# ProDoc_TB6612.net
KiCad netlist of a schematic drawn in EasyEDA Pro
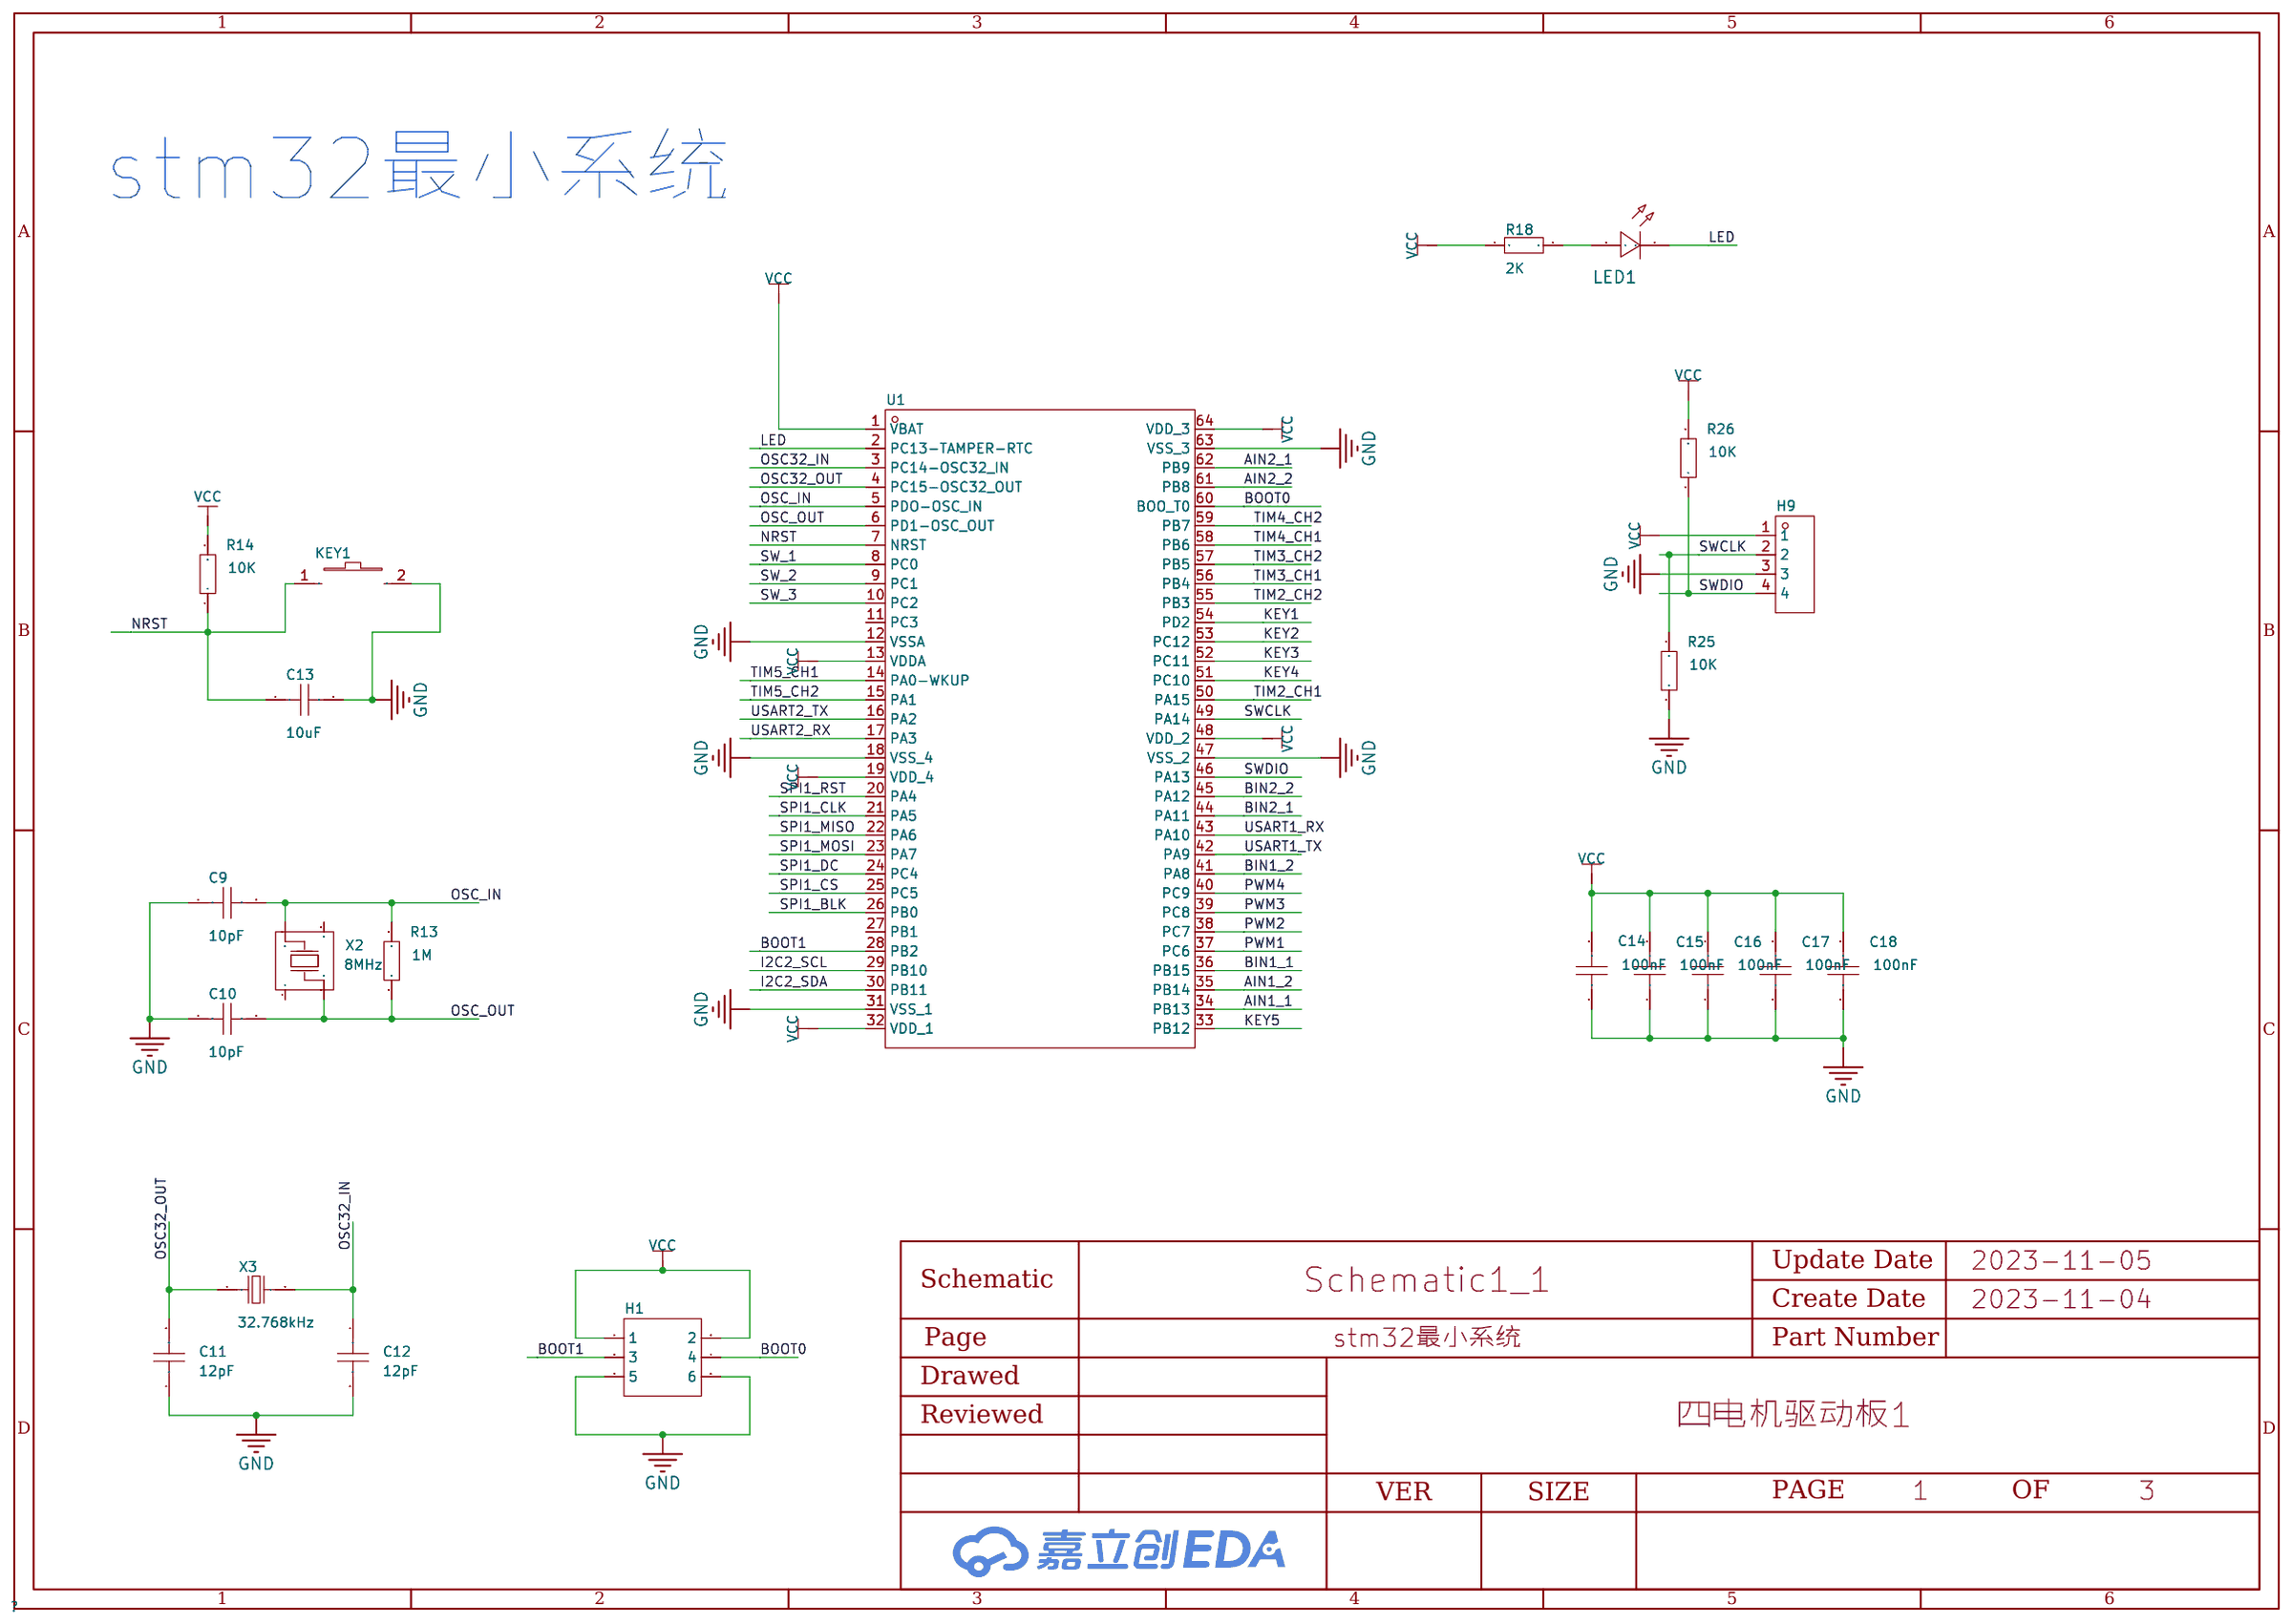
[diagram p0: stm32最小系统]
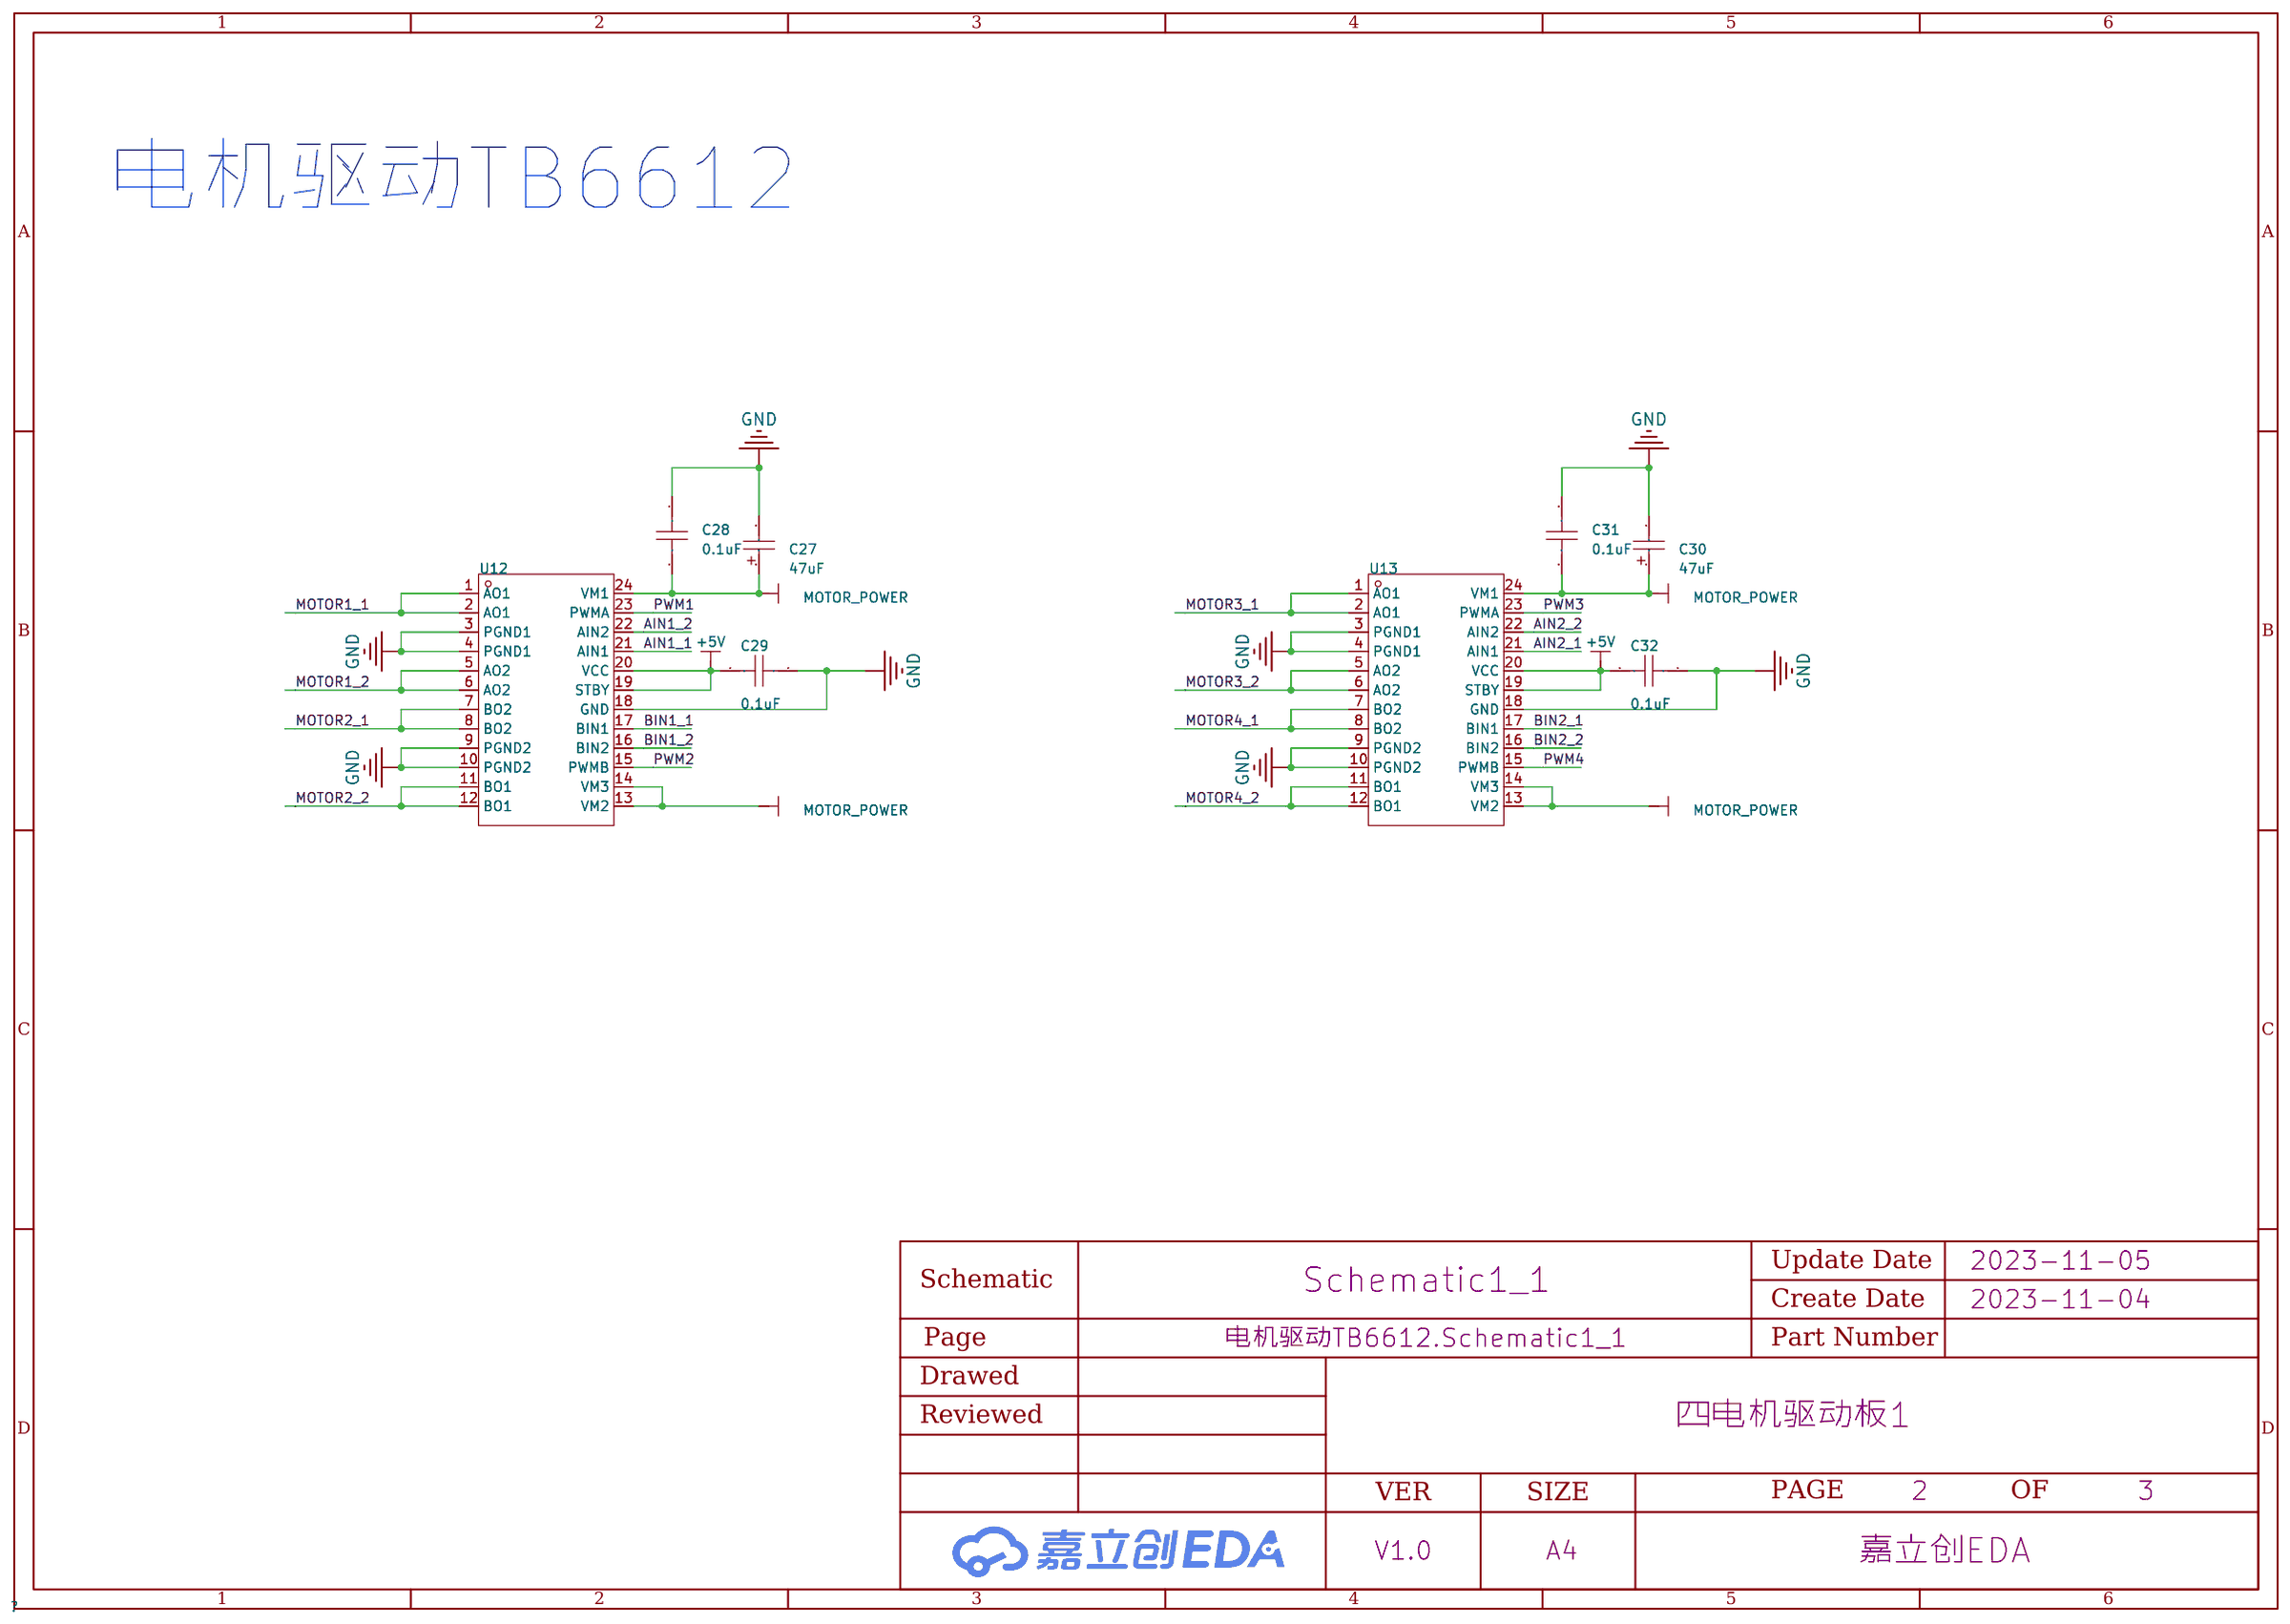
[diagram p1: 电机驱动TB6612]
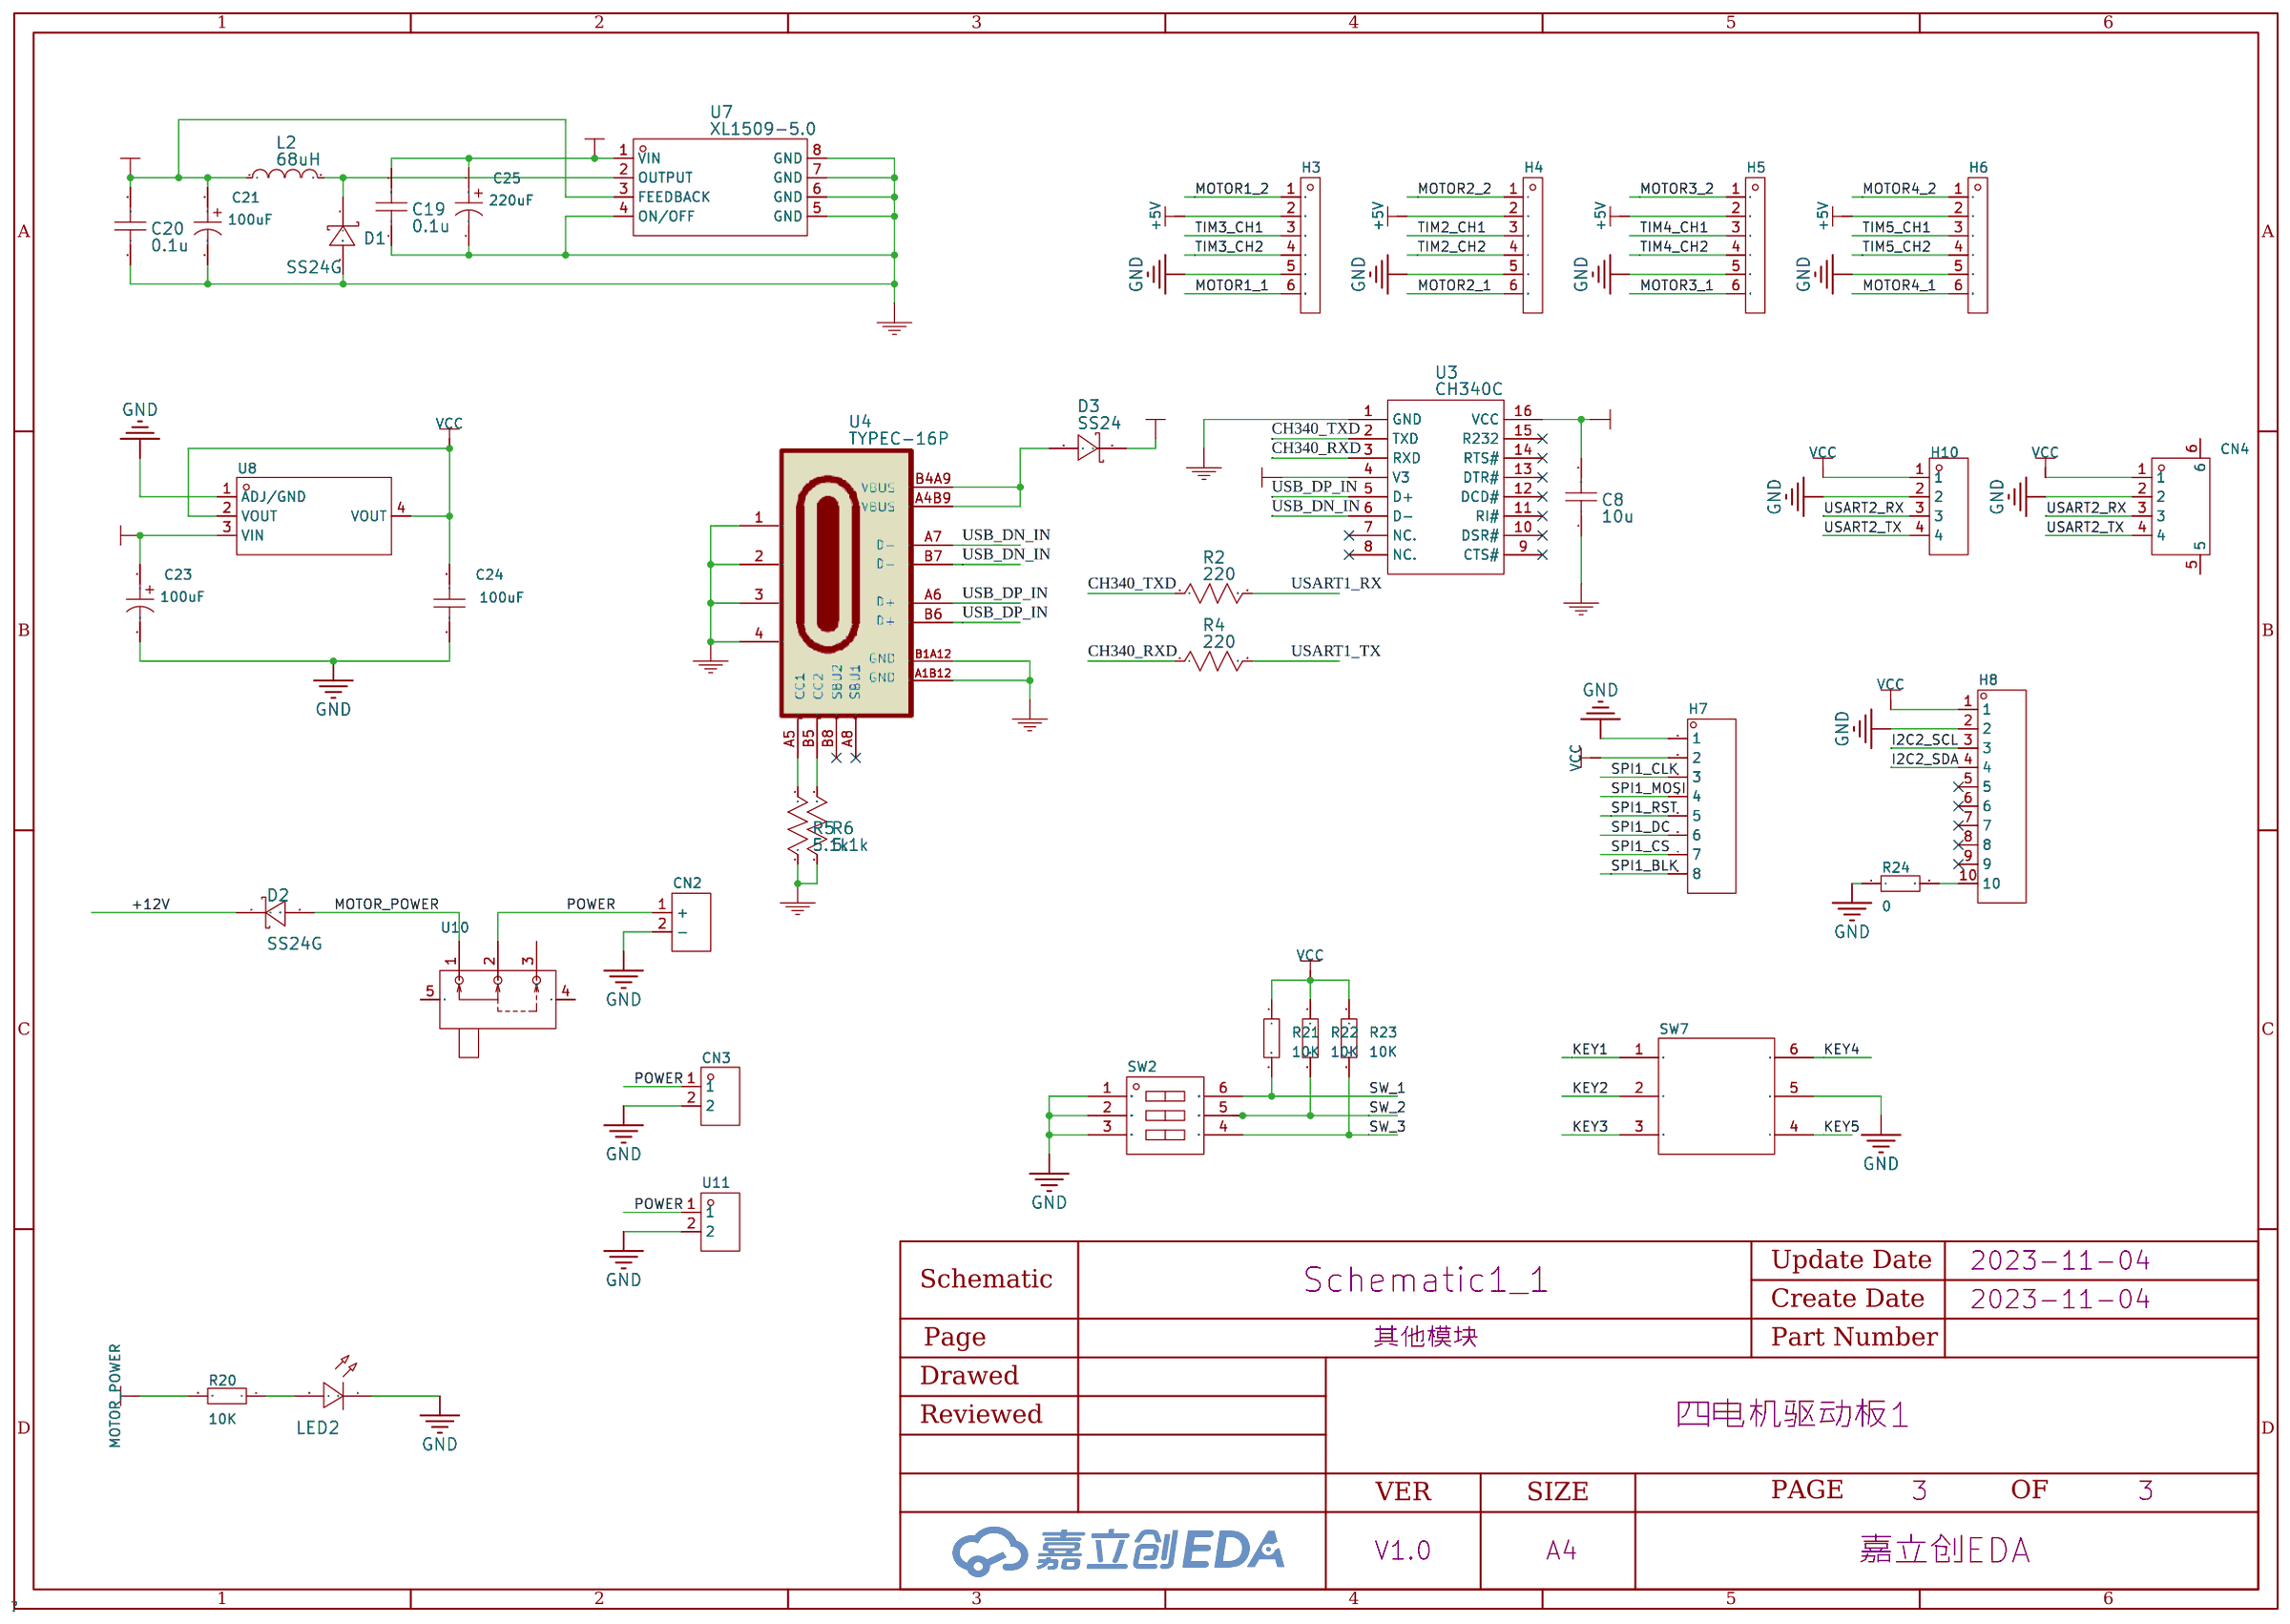
[diagram p2: 其他模块]

(export (version "E")
  (design (tool "Eeschema 10.0.6"))
  (components
    (comp (ref "C9")
      (value "10pF")
      (footprint "easyedapro:C0603")
      (libsource (lib "easyedapro") (part "C1210X7R475K630NT"))
    )
    (comp (ref "C10")
      (value "10pF")
      (footprint "easyedapro:C0603")
      (libsource (lib "easyedapro") (part "C1210X7R475K630NT"))
    )
    (comp (ref "C11")
      (value "12pF")
      (footprint "easyedapro:C0603")
      (libsource (lib "easyedapro") (part "C1210X7R475K630NT"))
    )
    (comp (ref "C12")
      (value "12pF")
      (footprint "easyedapro:C0603")
      (libsource (lib "easyedapro") (part "C1210X7R475K630NT"))
    )
    (comp (ref "C13")
      (value "10uF")
      (footprint "easyedapro:C0603")
      (fields
        (field (name "Manufacturer Part") "CC0603KRX7R9BB104")
        (field (name "Manufacturer") "YAGEO(国巨)")
        (field (name "Tolerance") "±10%")
      )
      (libsource (lib "easyedapro") (part "C1210X7R475K630NT"))
    )
    (comp (ref "C14")
      (value "100nF")
      (footprint "easyedapro:C0603")
      (libsource (lib "easyedapro") (part "C1210X7R475K630NT"))
    )
    (comp (ref "C15")
      (value "100nF")
      (footprint "easyedapro:C0603")
      (libsource (lib "easyedapro") (part "C1210X7R475K630NT"))
    )
    (comp (ref "C16")
      (value "100nF")
      (footprint "easyedapro:C0603")
      (libsource (lib "easyedapro") (part "C1210X7R475K630NT"))
    )
    (comp (ref "C17")
      (value "100nF")
      (footprint "easyedapro:C0603")
      (libsource (lib "easyedapro") (part "C1210X7R475K630NT"))
    )
    (comp (ref "C18")
      (value "100nF")
      (footprint "easyedapro:C0603")
      (libsource (lib "easyedapro") (part "C1210X7R475K630NT"))
    )
    (comp (ref "H1")
      (value "~")
      (footprint "easyedapro:HDR-TH_6P-P2.54-V-F-R2-C3-S2.54")
      (libsource (lib "easyedapro") (part "HDR-F-2.54_2x3"))
    )
    (comp (ref "H9")
      (value "~")
      (footprint "easyedapro:HDR-TH_4P-P2.54-V-M")
      (libsource (lib "easyedapro") (part "PZ254V-11-04P"))
    )
    (comp (ref "KEY1")
      (value "轻触开关3x4x2")
      (footprint "easyedapro:SW-SMD_L4.0-W2.9-LS5.0")
      (description "触点电流:50mA;额定电压(DC):12V;电路结构:单刀单掷;安装方式:立贴;按钮形状:圆形按钮;带灯:-;开关长度:4mm;开关宽度:3mm;开关高度:2mm;")
      (fields (field (name "Manufacturer") "国产"))
      (libsource (lib "easyedapro") (part "Switch3x4x2"))
    )
    (comp (ref "LED1")
      (value "~")
      (footprint "easyedapro:LED0805-RD_RED")
      (libsource (lib "easyedapro") (part "LED_R"))
    )
    (comp (ref "R13") (value "1M") (footprint "easyedapro:R0603") (libsource (lib "easyedapro") (part "电阻")))
    (comp (ref "R14") (value "10K") (footprint "easyedapro:R0603") (libsource (lib "easyedapro") (part "电阻")))
    (comp (ref "R18") (value "2K") (footprint "easyedapro:R0603") (libsource (lib "easyedapro") (part "电阻")))
    (comp (ref "R25") (value "10K") (footprint "easyedapro:R0603") (libsource (lib "easyedapro") (part "电阻")))
    (comp (ref "R26") (value "10K") (footprint "easyedapro:R0603") (libsource (lib "easyedapro") (part "电阻")))
    (comp (ref "U1")
      (value "~")
      (footprint "easyedapro:LQFP-64_L10.0-W10.0-P0.50-LS12.0-BL")
      (description "主频（MAX):72MHz;工作电压:2V ~ 3.6V;")
      (fields (field (name "Manufacturer Part") "STM32F103RCT6") (field (name "Manufacturer") "ST(意法半导体)"))
      (libsource (lib "easyedapro") (part "STM32F103RCT6"))
    )
    (comp (ref "X2")
      (value "8MHz")
      (footprint "easyedapro:OSC-SMD_4P-L3.2-W2.5-BL")
      (description "晶振类型:SMD 谐振器;频率:8MHz;频率公差:±10ppm;频率稳定度:±15ppm;负载电容:10pF;等效串联电阻(ESR):250Ω;工作温度:-;")
      (fields (field (name "Manufacturer Part") "TAXM8M4RDBCCT2T") (field (name "Manufacturer") "TAE(雅晶鑫)"))
      (libsource (lib "easyedapro") (part "TAXM8M4RDBCCT2T"))
    )
    (comp (ref "X3")
      (value "32.768kHz")
      (footprint "easyedapro:FC-135R_L3.2-W1.5")
      (description "晶振类型:贴片无源晶振;频率:32.768kHz;频率公差:±20ppm;负载电容:12.5pF;等效串联电阻(ESR):70kΩ;工作温度:-40~+85;")
      (fields (field (name "Manufacturer Part") "Q13FC1350000400") (field (name "Manufacturer") "EPSON(爱普生)"))
      (libsource (lib "easyedapro") (part "Q13FC1350000400"))
    )
    (comp (ref "C27")
      (value "47uF")
      (footprint "easyedapro:CAP-SMD_L6.0-W3.2-R-RD")
      (description "容值:47uF;精度:±10%;额定电压:16V;等效串联电阻:500mΩ@100kHz;")
      (fields (field (name "Manufacturer Part") "TAJC476K016RNJ") (field (name "Manufacturer") "Kyocera AVX"))
      (libsource (lib "easyedapro") (part "TAJC476K016RNJ"))
    )
    (comp (ref "C28")
      (value "0.1uF")
      (footprint "easyedapro:C0603")
      (libsource (lib "easyedapro") (part "C1210X7R475K630NT"))
    )
    (comp (ref "C29")
      (value "0.1uF")
      (footprint "easyedapro:C0603")
      (libsource (lib "easyedapro") (part "C1210X7R475K630NT"))
    )
    (comp (ref "C30")
      (value "47uF")
      (footprint "easyedapro:CAP-SMD_L6.0-W3.2-R-RD")
      (description "容值:47uF;精度:±10%;额定电压:16V;等效串联电阻:500mΩ@100kHz;")
      (fields (field (name "Manufacturer Part") "TAJC476K016RNJ") (field (name "Manufacturer") "Kyocera AVX"))
      (libsource (lib "easyedapro") (part "TAJC476K016RNJ"))
    )
    (comp (ref "C31")
      (value "0.1uF")
      (footprint "easyedapro:C0603")
      (libsource (lib "easyedapro") (part "C1210X7R475K630NT"))
    )
    (comp (ref "C32")
      (value "0.1uF")
      (footprint "easyedapro:C0603")
      (libsource (lib "easyedapro") (part "C1210X7R475K630NT"))
    )
    (comp (ref "U12")
      (value "TB6612FNG(O,C,8,EL")
      (footprint "easyedapro:SSOP-24_L8.4-W5.8-P0.65-LS7.8-BL")
      (description "双直流电机驱动器集成电路")
      (fields (field (name "Manufacturer") "TOSHIBA(东芝)"))
      (libsource (lib "easyedapro") (part "TB6612FNG(O,C,8,EL"))
    )
    (comp (ref "U13")
      (value "TB6612FNG(O,C,8,EL")
      (footprint "easyedapro:SSOP-24_L8.4-W5.8-P0.65-LS7.8-BL")
      (description "双直流电机驱动器集成电路")
      (fields (field (name "Manufacturer") "TOSHIBA(东芝)"))
      (libsource (lib "easyedapro") (part "TB6612FNG(O,C,8,EL"))
    )
    (comp (ref "C8") (value "10u") (footprint "easyedapro:C0603") (libsource (lib "easyedapro") (part "10u")))
    (comp (ref "C19")
      (value "0.1u")
      (footprint "easyedapro:C0603")
      (libsource (lib "easyedapro") (part "0.1u"))
    )
    (comp (ref "C20")
      (value "0.1u")
      (footprint "easyedapro:C0603")
      (libsource (lib "easyedapro") (part "0.1u"))
    )
    (comp (ref "C21")
      (value "100uF")
      (footprint "easyedapro:CAP-SMD_BD6.3-L6.6-W6.6-LS7.3-FD")
      (description "容值:100uF;精度:±20%;额定电压:16V;电容体直径:6.3mm;电容体长度:7.7mm;纹波电流:85mA@120Hz;工作寿命:2000hrs@105;工作温度:-55~+105;")
      (fields
        (field (name "Manufacturer Part") "XT100UF16V90RV0074")
        (field (name "Manufacturer") "KNSCHA(科尼盛)")
      )
      (libsource (lib "easyedapro") (part "XT100UF16V90RV0074"))
    )
    (comp (ref "C23")
      (value "100uF")
      (footprint "easyedapro:CAP-SMD_BD6.3-L6.6-W6.6-LS7.3-FD")
      (description "容值:100uF;精度:±20%;额定电压:16V;电容体直径:6.3mm;电容体长度:7.7mm;纹波电流:85mA@120Hz;工作寿命:2000hrs@105;工作温度:-55~+105;")
      (fields
        (field (name "Manufacturer Part") "XT100UF16V90RV0074")
        (field (name "Manufacturer") "KNSCHA(科尼盛)")
      )
      (libsource (lib "easyedapro") (part "XT100UF16V90RV0074"))
    )
    (comp (ref "C24")
      (value "100uF")
      (footprint "easyedapro:C0603")
      (libsource (lib "easyedapro") (part "C1210X7R475K630NT"))
    )
    (comp (ref "C25")
      (value "220uF")
      (footprint "easyedapro:CAP-SMD_BD6.3-L6.6-W6.6-LS7.3-FD")
      (description "容值:220uF;额定电压:25V;电容体直径:-;电容体长度:-;纹波电流:-;等效串联电阻:-;工作寿命:-;")
      (fields
        (field (name "Manufacturer Part") "XT220UF25V90RV0075")
        (field (name "Manufacturer") "KNSCHA(科尼盛)")
      )
      (libsource (lib "easyedapro") (part "XT220UF25V90RV0075"))
    )
    (comp (ref "CN2")
      (value "XT30UPB-F")
      (footprint "easyedapro:CONN-TH_XT30UPB-F")
      (description "模型插头连接器")
      (fields (field (name "Manufacturer") "AMASS(艾迈斯)"))
      (libsource (lib "easyedapro") (part "XT30UPB-F"))
    )
    (comp (ref "CN3")
      (value "XT30U-M")
      (footprint "easyedapro:CONN-TH_XT30U-M")
      (description "模型插头轻量版锂电池插头")
      (fields (field (name "Manufacturer") "AMASS(艾迈斯)"))
      (libsource (lib "easyedapro") (part "XT30U-M"))
    )
    (comp (ref "CN4")
      (value "PH-4P卧贴")
      (footprint "easyedapro:CONN-SMD_PH2.0-4PWB")
      (description "参考系列:PH;间距:2mm;插针结构:1x4P;排数:1;每排PIN数:4;行距:-;安装方式:-;触头材质:-;")
      (fields (field (name "Manufacturer") "BOOMELE(博穆精密)"))
      (libsource (lib "easyedapro") (part "PH2.0-4PWB卧式"))
    )
    (comp (ref "D1")
      (value "SS24G")
      (footprint "easyedapro:SMA_L4.4-W2.8-LS5.4-RD")
      (fields (field (name "Manufacturer") "SK"))
      (libsource (lib "easyedapro") (part "SS24G"))
    )
    (comp (ref "D2")
      (value "SS24G")
      (footprint "easyedapro:SMA_L4.4-W2.8-LS5.4-RD")
      (fields (field (name "Manufacturer") "SK"))
      (libsource (lib "easyedapro") (part "SS24G"))
    )
    (comp (ref "D3")
      (value "SS24")
      (footprint "easyedapro:SMA_L4.3-W2.6-LS5.2-RD")
      (fields (field (name "Manufacturer") "MDD"))
      (libsource (lib "easyedapro") (part "SS24"))
    )
    (comp (ref "H3")
      (value "~")
      (footprint "easyedapro:CONN-TH_XH-6AW")
      (description "参考系列:XH;间距:2.5mm;插针结构:1x6P;排数:1;每排PIN数:6;行距:-;安装方式:-;触头材质:-;")
      (fields (field (name "Manufacturer Part") "XH-6AW") (field (name "Manufacturer") "BOOMELE(博穆精密)"))
      (libsource (lib "easyedapro") (part "6P接插件"))
    )
    (comp (ref "H4")
      (value "~")
      (footprint "easyedapro:CONN-TH_XH-6AW")
      (description "参考系列:XH;间距:2.5mm;插针结构:1x6P;排数:1;每排PIN数:6;行距:-;安装方式:-;触头材质:-;")
      (fields (field (name "Manufacturer Part") "XH-6AW") (field (name "Manufacturer") "BOOMELE(博穆精密)"))
      (libsource (lib "easyedapro") (part "6P接插件"))
    )
    (comp (ref "H5")
      (value "~")
      (footprint "easyedapro:CONN-TH_XH-6AW")
      (description "参考系列:XH;间距:2.5mm;插针结构:1x6P;排数:1;每排PIN数:6;行距:-;安装方式:-;触头材质:-;")
      (fields (field (name "Manufacturer Part") "XH-6AW") (field (name "Manufacturer") "BOOMELE(博穆精密)"))
      (libsource (lib "easyedapro") (part "6P接插件"))
    )
    (comp (ref "H6")
      (value "~")
      (footprint "easyedapro:CONN-TH_XH-6AW")
      (description "参考系列:XH;间距:2.5mm;插针结构:1x6P;排数:1;每排PIN数:6;行距:-;安装方式:-;触头材质:-;")
      (fields (field (name "Manufacturer Part") "XH-6AW") (field (name "Manufacturer") "BOOMELE(博穆精密)"))
      (libsource (lib "easyedapro") (part "6P接插件"))
    )
    (comp (ref "H7")
      (value "~")
      (footprint "easyedapro:HDR-TH_8P-P2.54-V-M")
      (libsource (lib "easyedapro") (part "Header-Male-2.54_1x8"))
    )
    (comp (ref "H8")
      (value "~")
      (footprint "easyedapro:HDR-TH_10P-P2.54-V-M-1")
      (libsource (lib "easyedapro") (part "Header-Male-2.54_1x10"))
    )
    (comp (ref "H10")
      (value "~")
      (footprint "easyedapro:HDR-TH_4P-P2.54-V-F")
      (libsource (lib "easyedapro") (part "2.54-1*4P母"))
    )
    (comp (ref "L2")
      (value "68uH")
      (footprint "easyedapro:IND-SMD_L5.8-W5.2_CD54T125NP-100MC")
      (fields (field (name "Manufacturer Part") "CD54T125NP-100MC") (field (name "Manufacturer") "Sumida"))
      (libsource (lib "easyedapro") (part "68uH"))
    )
    (comp (ref "LED2")
      (value "~")
      (footprint "easyedapro:LED0805-RD_RED")
      (libsource (lib "easyedapro") (part "LED_R"))
    )
    (comp (ref "R2") (value "220") (footprint "easyedapro:R0603") (libsource (lib "easyedapro") (part "220")))
    (comp (ref "R4") (value "220") (footprint "easyedapro:R0603") (libsource (lib "easyedapro") (part "220")))
    (comp (ref "R5")
      (value "5.1k")
      (footprint "easyedapro:R0603")
      (libsource (lib "easyedapro") (part "5.1k"))
    )
    (comp (ref "R6")
      (value "5.1k")
      (footprint "easyedapro:R0603")
      (libsource (lib "easyedapro") (part "5.1k"))
    )
    (comp (ref "R20") (value "10K") (footprint "easyedapro:R0603") (libsource (lib "easyedapro") (part "电阻")))
    (comp (ref "R21") (value "10K") (footprint "easyedapro:R0603") (libsource (lib "easyedapro") (part "电阻")))
    (comp (ref "R22") (value "10K") (footprint "easyedapro:R0603") (libsource (lib "easyedapro") (part "电阻")))
    (comp (ref "R23") (value "10K") (footprint "easyedapro:R0603") (libsource (lib "easyedapro") (part "电阻")))
    (comp (ref "R24") (value "0") (footprint "easyedapro:R0603") (libsource (lib "easyedapro") (part "电阻")))
    (comp (ref "SW2")
      (value "TO-03")
      (footprint "easyedapro:SW-SMD_6P-L7.6-W6.3-P2.54-LS9.8")
      (description "拨码开关贴片黑色03P-3PIN间距2.54mm立式贴片正拨平拨3位SMD")
      (fields (field (name "Manufacturer") "Yuandi(台湾元迪)"))
      (libsource (lib "easyedapro") (part "TO-03"))
    )
    (comp (ref "SW7")
      (value "7*7*5-6P-L WX")
      (footprint "easyedapro:SW-SMD_6P-L7.0-W7.0-P1.40-LS7.4")
      (fields (field (name "Manufacturer") "SHOU HAN(首韩)"))
      (libsource (lib "easyedapro") (part "7*7*5-6P-L WX"))
    )
    (comp (ref "U3")
      (value "CH340C")
      (footprint "easyedapro:SOP-16_L10.0-W3.9-P1.27-LS6.0-BL")
      (fields (field (name "Manufacturer") "WCH(南京沁恒)"))
      (libsource (lib "easyedapro") (part "CH340C"))
    )
    (comp (ref "U4")
      (value "TYPEC-16P")
      (footprint "easyedapro:TYPEC")
      (libsource (lib "easyedapro") (part "TYPEC-16P"))
    )
    (comp (ref "U7")
      (value "XL1509-5.0")
      (footprint "easyedapro:SOIC-8_L5.0-W4.0-P1.27-LS6.0-BL")
      (fields (field (name "Manufacturer") "UMW(友台半导体)"))
      (libsource (lib "easyedapro") (part "XL1509-5.0"))
    )
    (comp (ref "U8")
      (value "AMS1117-3.3")
      (footprint "easyedapro:SOT-223_L6.5-W3.5-P2.30-LS7.0-BR")
      (fields (field (name "Manufacturer") "PUOLOP(迪浦)"))
      (libsource (lib "easyedapro") (part "AMS1117-3.3_C351785"))
    )
    (comp (ref "U10")
      (value "SS-12F23-G4")
      (footprint "easyedapro:SW-TH_SS-12F23-G040")
      (description "电路结构:单刀双掷;安装方式:卧插;开关颜色:黑色;滑钮形状:矩形柱状;引脚样式:PC引脚;开关长度:13mm;开关宽度:5.8mm;开关高度:9mm;")
      (fields (field (name "Manufacturer") "DEALON(德艺隆)"))
      (libsource (lib "easyedapro") (part "SS-12F23-G4"))
    )
    (comp (ref "U11")
      (value "KF127-5.08-2P")
      (footprint "easyedapro:CONN-TH_P5.08_KF127-5.08-2P")
      (fields (field (name "Manufacturer") "KEFA(科发)"))
      (libsource (lib "easyedapro") (part "KF127-5.08-2P"))
    )
  )
  (nets
    (net (code "1") (name "+5V") (class "Default")
      (node (ref "C20") (pin "2") (pinfunction "2_2") (pintype "input"))
      (node (ref "C21") (pin "1") (pinfunction "1_1") (pintype "input"))
      (node (ref "C23") (pin "1") (pinfunction "1_1") (pintype "input"))
      (node (ref "C29") (pin "2") (pinfunction "2_2") (pintype "input"))
      (node (ref "C32") (pin "2") (pinfunction "2_2") (pintype "input"))
      (node (ref "D3") (pin "1") (pinfunction "K_1") (pintype "input"))
      (node (ref "H3") (pin "2") (pinfunction "2_2") (pintype "input"))
      (node (ref "H4") (pin "2") (pinfunction "2_2") (pintype "input"))
      (node (ref "H5") (pin "2") (pinfunction "2_2") (pintype "input"))
      (node (ref "H6") (pin "2") (pinfunction "2_2") (pintype "input"))
      (node (ref "L2") (pin "1") (pinfunction "1_1") (pintype "input"))
      (node (ref "U12") (pin "19") (pinfunction "STBY_19") (pintype "input"))
      (node (ref "U12") (pin "20") (pinfunction "VCC_20") (pintype "input"))
      (node (ref "U13") (pin "19") (pinfunction "STBY_19") (pintype "input"))
      (node (ref "U13") (pin "20") (pinfunction "VCC_20") (pintype "input"))
      (node (ref "U7") (pin "3") (pinfunction "FEEDBACK_3") (pintype "input"))
      (node (ref "U8") (pin "3") (pinfunction "VIN_3") (pintype "input"))
    )
    (net (code "2") (name "+12V") (class "Default")
      (node (ref "C19") (pin "2") (pinfunction "2_2") (pintype "input"))
      (node (ref "C25") (pin "1") (pinfunction "1_1") (pintype "input"))
      (node (ref "D2") (pin "1") (pinfunction "1_1") (pintype "input"))
      (node (ref "U7") (pin "1") (pinfunction "VIN_1") (pintype "input"))
    )
    (net (code "3") (name "AIN1_1") (class "Default")
      (node (ref "U1") (pin "34") (pinfunction "PB13_34") (pintype "input"))
      (node (ref "U12") (pin "21") (pinfunction "AIN1_21") (pintype "input"))
    )
    (net (code "4") (name "AIN1_2") (class "Default")
      (node (ref "U1") (pin "35") (pinfunction "PB14_35") (pintype "input"))
      (node (ref "U12") (pin "22") (pinfunction "AIN2_22") (pintype "input"))
    )
    (net (code "5") (name "AIN2_1") (class "Default")
      (node (ref "U1") (pin "62") (pinfunction "PB9_62") (pintype "input"))
      (node (ref "U13") (pin "21") (pinfunction "AIN1_21") (pintype "input"))
    )
    (net (code "6") (name "AIN2_2") (class "Default")
      (node (ref "U1") (pin "61") (pinfunction "PB8_61") (pintype "input"))
      (node (ref "U13") (pin "22") (pinfunction "AIN2_22") (pintype "input"))
    )
    (net (code "7") (name "BIN1_1") (class "Default")
      (node (ref "U1") (pin "36") (pinfunction "PB15_36") (pintype "input"))
      (node (ref "U12") (pin "17") (pinfunction "BIN1_17") (pintype "input"))
    )
    (net (code "8") (name "BIN1_2") (class "Default")
      (node (ref "U1") (pin "41") (pinfunction "PA8_41") (pintype "input"))
      (node (ref "U12") (pin "16") (pinfunction "BIN2_16") (pintype "input"))
    )
    (net (code "9") (name "BIN2_1") (class "Default")
      (node (ref "U1") (pin "44") (pinfunction "PA11_44") (pintype "input"))
      (node (ref "U13") (pin "17") (pinfunction "BIN1_17") (pintype "input"))
    )
    (net (code "10") (name "BIN2_2") (class "Default")
      (node (ref "U1") (pin "45") (pinfunction "PA12_45") (pintype "input"))
      (node (ref "U13") (pin "16") (pinfunction "BIN2_16") (pintype "input"))
    )
    (net (code "11") (name "BOOT0") (class "Default")
      (node (ref "H1") (pin "4") (pinfunction "4_4") (pintype "input"))
      (node (ref "U1") (pin "60") (pinfunction "BOO_T0_60") (pintype "input"))
    )
    (net (code "12") (name "BOOT1") (class "Default")
      (node (ref "H1") (pin "3") (pinfunction "3_3") (pintype "input"))
      (node (ref "U1") (pin "28") (pinfunction "PB2_28") (pintype "input"))
    )
    (net (code "13") (name "CH340_RXD") (class "Default")
      (node (ref "R4") (pin "1") (pinfunction "1_1") (pintype "input"))
      (node (ref "U3") (pin "3") (pinfunction "RXD_3") (pintype "input"))
    )
    (net (code "14") (name "CH340_TXD") (class "Default")
      (node (ref "R2") (pin "1") (pinfunction "1_1") (pintype "input"))
      (node (ref "U3") (pin "2") (pinfunction "TXD_2") (pintype "input"))
    )
    (net (code "15") (name "GND") (class "Default")
      (node (ref "C10") (pin "1") (pinfunction "1_1") (pintype "input"))
      (node (ref "C11") (pin "1") (pinfunction "1_1") (pintype "input"))
      (node (ref "C12") (pin "2") (pinfunction "2_2") (pintype "input"))
      (node (ref "C13") (pin "2") (pinfunction "2_2") (pintype "input"))
      (node (ref "C14") (pin "1") (pinfunction "1_1") (pintype "input"))
      (node (ref "C15") (pin "1") (pinfunction "1_1") (pintype "input"))
      (node (ref "C16") (pin "1") (pinfunction "1_1") (pintype "input"))
      (node (ref "C17") (pin "1") (pinfunction "1_1") (pintype "input"))
      (node (ref "C18") (pin "1") (pinfunction "1_1") (pintype "input"))
      (node (ref "C19") (pin "1") (pinfunction "1_1") (pintype "input"))
      (node (ref "C20") (pin "1") (pinfunction "1_1") (pintype "input"))
      (node (ref "C21") (pin "2") (pinfunction "2_2") (pintype "input"))
      (node (ref "C23") (pin "2") (pinfunction "2_2") (pintype "input"))
      (node (ref "C24") (pin "1") (pinfunction "1_1") (pintype "input"))
      (node (ref "C25") (pin "2") (pinfunction "2_2") (pintype "input"))
      (node (ref "C27") (pin "2") (pinfunction "2_2") (pintype "input"))
      (node (ref "C28") (pin "1") (pinfunction "1_1") (pintype "input"))
      (node (ref "C29") (pin "1") (pinfunction "1_1") (pintype "input"))
      (node (ref "C30") (pin "2") (pinfunction "2_2") (pintype "input"))
      (node (ref "C31") (pin "1") (pinfunction "1_1") (pintype "input"))
      (node (ref "C32") (pin "1") (pinfunction "1_1") (pintype "input"))
      (node (ref "C8") (pin "1") (pinfunction "1_1") (pintype "input"))
      (node (ref "C9") (pin "1") (pinfunction "1_1") (pintype "input"))
      (node (ref "CN2") (pin "2") (pinfunction "-_2") (pintype "input"))
      (node (ref "CN3") (pin "2") (pinfunction "2_2") (pintype "input"))
      (node (ref "CN4") (pin "2") (pinfunction "2_2") (pintype "input"))
      (node (ref "D1") (pin "2") (pinfunction "2_2") (pintype "input"))
      (node (ref "H1") (pin "5") (pinfunction "5_5") (pintype "input"))
      (node (ref "H1") (pin "6") (pinfunction "6_6") (pintype "input"))
      (node (ref "H10") (pin "2") (pinfunction "2_2") (pintype "unspecified"))
      (node (ref "H3") (pin "5") (pinfunction "5_5") (pintype "input"))
      (node (ref "H4") (pin "5") (pinfunction "5_5") (pintype "input"))
      (node (ref "H5") (pin "5") (pinfunction "5_5") (pintype "input"))
      (node (ref "H6") (pin "5") (pinfunction "5_5") (pintype "input"))
      (node (ref "H7") (pin "1") (pinfunction "1_1") (pintype "input"))
      (node (ref "H8") (pin "2") (pinfunction "2_2") (pintype "input"))
      (node (ref "H9") (pin "3") (pinfunction "3_3") (pintype "input"))
      (node (ref "KEY1") (pin "2") (pinfunction "2_2") (pintype "input"))
      (node (ref "LED2") (pin "1") (pinfunction "C_1") (pintype "input"))
      (node (ref "R24") (pin "1") (pinfunction "1_1") (pintype "input"))
      (node (ref "R25") (pin "1") (pinfunction "1_1") (pintype "input"))
      (node (ref "R5") (pin "1") (pinfunction "1_1") (pintype "input"))
      (node (ref "R6") (pin "1") (pinfunction "1_1") (pintype "input"))
      (node (ref "SW2") (pin "1") (pinfunction "PIN1_1") (pintype "input"))
      (node (ref "SW2") (pin "2") (pinfunction "PIN2_2") (pintype "input"))
      (node (ref "SW2") (pin "3") (pinfunction "PIN3_3") (pintype "input"))
      (node (ref "SW7") (pin "5") (pinfunction "5_5") (pintype "input"))
      (node (ref "U1") (pin "12") (pinfunction "VSSA_12") (pintype "input"))
      (node (ref "U1") (pin "18") (pinfunction "VSS_4_18") (pintype "input"))
      (node (ref "U1") (pin "31") (pinfunction "VSS_1_31") (pintype "input"))
      (node (ref "U1") (pin "47") (pinfunction "VSS_2_47") (pintype "input"))
      (node (ref "U1") (pin "63") (pinfunction "VSS_3_63") (pintype "input"))
      (node (ref "U11") (pin "2") (pinfunction "2_2") (pintype "input"))
      (node (ref "U12") (pin "10") (pinfunction "PGND2_10") (pintype "input"))
      (node (ref "U12") (pin "18") (pinfunction "GND_18") (pintype "input"))
      (node (ref "U12") (pin "3") (pinfunction "PGND1_3") (pintype "input"))
      (node (ref "U12") (pin "4") (pinfunction "PGND1_4") (pintype "input"))
      (node (ref "U12") (pin "9") (pinfunction "PGND2_9") (pintype "input"))
      (node (ref "U13") (pin "10") (pinfunction "PGND2_10") (pintype "input"))
      (node (ref "U13") (pin "18") (pinfunction "GND_18") (pintype "input"))
      (node (ref "U13") (pin "3") (pinfunction "PGND1_3") (pintype "input"))
      (node (ref "U13") (pin "4") (pinfunction "PGND1_4") (pintype "input"))
      (node (ref "U13") (pin "9") (pinfunction "PGND2_9") (pintype "input"))
      (node (ref "U3") (pin "1") (pinfunction "GND_1") (pintype "input"))
      (node (ref "U4") (pin "1") (pinfunction "1_1") (pintype "input"))
      (node (ref "U4") (pin "2") (pinfunction "1_2") (pintype "input"))
      (node (ref "U4") (pin "3") (pinfunction "1_3") (pintype "input"))
      (node (ref "U4") (pin "4") (pinfunction "1_4") (pintype "input"))
      (node (ref "U4") (pin "A1B12") (pinfunction "1_A1B12") (pintype "input"))
      (node (ref "U4") (pin "B1A12") (pinfunction "1_B1A12") (pintype "input"))
      (node (ref "U7") (pin "4") (pinfunction "ON/OFF_4") (pintype "input"))
      (node (ref "U7") (pin "5") (pinfunction "GND_5") (pintype "input"))
      (node (ref "U7") (pin "6") (pinfunction "GND_6") (pintype "input"))
      (node (ref "U7") (pin "7") (pinfunction "GND_7") (pintype "input"))
      (node (ref "U7") (pin "8") (pinfunction "GND_8") (pintype "input"))
      (node (ref "U8") (pin "1") (pinfunction "ADJ/GND_1") (pintype "input"))
    )
    (net (code "16") (name "I2C2_SCL") (class "Default")
      (node (ref "H8") (pin "3") (pinfunction "3_3") (pintype "input"))
      (node (ref "U1") (pin "29") (pinfunction "PB10_29") (pintype "input"))
    )
    (net (code "17") (name "I2C2_SDA") (class "Default")
      (node (ref "H8") (pin "4") (pinfunction "4_4") (pintype "input"))
      (node (ref "U1") (pin "30") (pinfunction "PB11_30") (pintype "input"))
    )
    (net (code "18") (name "KEY1") (class "Default")
      (node (ref "SW7") (pin "1") (pinfunction "1_1") (pintype "input"))
      (node (ref "U1") (pin "54") (pinfunction "PD2_54") (pintype "input"))
    )
    (net (code "19") (name "KEY2") (class "Default")
      (node (ref "SW7") (pin "2") (pinfunction "2_2") (pintype "input"))
      (node (ref "U1") (pin "53") (pinfunction "PC12_53") (pintype "input"))
    )
    (net (code "20") (name "KEY3") (class "Default")
      (node (ref "SW7") (pin "3") (pinfunction "3_3") (pintype "input"))
      (node (ref "U1") (pin "52") (pinfunction "PC11_52") (pintype "input"))
    )
    (net (code "21") (name "KEY4") (class "Default")
      (node (ref "SW7") (pin "6") (pinfunction "6_6") (pintype "input"))
      (node (ref "U1") (pin "51") (pinfunction "PC10_51") (pintype "input"))
    )
    (net (code "22") (name "KEY5") (class "Default")
      (node (ref "SW7") (pin "4") (pinfunction "4_4") (pintype "input"))
      (node (ref "U1") (pin "33") (pinfunction "PB12_33") (pintype "input"))
    )
    (net (code "23") (name "LED") (class "Default")
      (node (ref "LED1") (pin "1") (pinfunction "C_1") (pintype "input"))
      (node (ref "U1") (pin "2") (pinfunction "PC13-TAMPER-RTC_2") (pintype "input"))
    )
    (net (code "24") (name "MOTOR1_1") (class "Default")
      (node (ref "H3") (pin "6") (pinfunction "6_6") (pintype "input"))
      (node (ref "U12") (pin "1") (pinfunction "AO1_1") (pintype "input"))
      (node (ref "U12") (pin "2") (pinfunction "AO1_2") (pintype "input"))
    )
    (net (code "25") (name "MOTOR1_2") (class "Default")
      (node (ref "H3") (pin "1") (pinfunction "1_1") (pintype "input"))
      (node (ref "U12") (pin "5") (pinfunction "AO2_5") (pintype "input"))
      (node (ref "U12") (pin "6") (pinfunction "AO2_6") (pintype "input"))
    )
    (net (code "26") (name "MOTOR2_1") (class "Default")
      (node (ref "H4") (pin "6") (pinfunction "6_6") (pintype "input"))
      (node (ref "U12") (pin "7") (pinfunction "BO2_7") (pintype "input"))
      (node (ref "U12") (pin "8") (pinfunction "BO2_8") (pintype "input"))
    )
    (net (code "27") (name "MOTOR2_2") (class "Default")
      (node (ref "H4") (pin "1") (pinfunction "1_1") (pintype "input"))
      (node (ref "U12") (pin "11") (pinfunction "BO1_11") (pintype "input"))
      (node (ref "U12") (pin "12") (pinfunction "BO1_12") (pintype "input"))
    )
    (net (code "28") (name "MOTOR3_1") (class "Default")
      (node (ref "H5") (pin "6") (pinfunction "6_6") (pintype "input"))
      (node (ref "U13") (pin "1") (pinfunction "AO1_1") (pintype "input"))
      (node (ref "U13") (pin "2") (pinfunction "AO1_2") (pintype "input"))
    )
    (net (code "29") (name "MOTOR3_2") (class "Default")
      (node (ref "H5") (pin "1") (pinfunction "1_1") (pintype "input"))
      (node (ref "U13") (pin "5") (pinfunction "AO2_5") (pintype "input"))
      (node (ref "U13") (pin "6") (pinfunction "AO2_6") (pintype "input"))
    )
    (net (code "30") (name "MOTOR4_1") (class "Default")
      (node (ref "H6") (pin "6") (pinfunction "6_6") (pintype "input"))
      (node (ref "U13") (pin "7") (pinfunction "BO2_7") (pintype "input"))
      (node (ref "U13") (pin "8") (pinfunction "BO2_8") (pintype "input"))
    )
    (net (code "31") (name "MOTOR4_2") (class "Default")
      (node (ref "H6") (pin "1") (pinfunction "1_1") (pintype "input"))
      (node (ref "U13") (pin "11") (pinfunction "BO1_11") (pintype "input"))
      (node (ref "U13") (pin "12") (pinfunction "BO1_12") (pintype "input"))
    )
    (net (code "32") (name "MOTOR_POWER") (class "Default")
      (node (ref "C27") (pin "1") (pinfunction "1_1") (pintype "input"))
      (node (ref "C28") (pin "2") (pinfunction "2_2") (pintype "input"))
      (node (ref "C30") (pin "1") (pinfunction "1_1") (pintype "input"))
      (node (ref "C31") (pin "2") (pinfunction "2_2") (pintype "input"))
      (node (ref "D2") (pin "2") (pinfunction "2_2") (pintype "input"))
      (node (ref "R20") (pin "2") (pinfunction "2_2") (pintype "input"))
      (node (ref "U10") (pin "1") (pinfunction "1_1") (pintype "input"))
      (node (ref "U12") (pin "13") (pinfunction "VM2_13") (pintype "input"))
      (node (ref "U12") (pin "14") (pinfunction "VM3_14") (pintype "input"))
      (node (ref "U12") (pin "24") (pinfunction "VM1_24") (pintype "input"))
      (node (ref "U13") (pin "13") (pinfunction "VM2_13") (pintype "input"))
      (node (ref "U13") (pin "14") (pinfunction "VM3_14") (pintype "input"))
      (node (ref "U13") (pin "24") (pinfunction "VM1_24") (pintype "input"))
    )
    (net (code "33") (name "NRST") (class "Default")
      (node (ref "C13") (pin "1") (pinfunction "1_1") (pintype "input"))
      (node (ref "KEY1") (pin "1") (pinfunction "1_1") (pintype "input"))
      (node (ref "R14") (pin "1") (pinfunction "1_1") (pintype "input"))
      (node (ref "U1") (pin "7") (pinfunction "NRST_7") (pintype "input"))
    )
    (net (code "34") (name "Net-(D3-A)") (class "Default")
      (node (ref "D3") (pin "2") (pinfunction "A_2") (pintype "input"))
      (node (ref "U4") (pin "A4B9") (pinfunction "1_A4B9") (pintype "input"))
      (node (ref "U4") (pin "B4A9") (pinfunction "1_B4A9") (pintype "input"))
    )
    (net (code "35") (name "Net-(H8-Pad10)") (class "Default")
      (node (ref "H8") (pin "10") (pinfunction "10_10") (pintype "input"))
      (node (ref "R24") (pin "2") (pinfunction "2_2") (pintype "input"))
    )
    (net (code "36") (name "Net-(LED1-A)") (class "Default")
      (node (ref "LED1") (pin "2") (pinfunction "A_2") (pintype "input"))
      (node (ref "R18") (pin "1") (pinfunction "1_1") (pintype "input"))
    )
    (net (code "37") (name "Net-(LED2-A)") (class "Default")
      (node (ref "LED2") (pin "2") (pinfunction "A_2") (pintype "input"))
      (node (ref "R20") (pin "1") (pinfunction "1_1") (pintype "input"))
    )
    (net (code "38") (name "Net-(R5-Pad2)") (class "Default")
      (node (ref "R5") (pin "2") (pinfunction "2_2") (pintype "input"))
      (node (ref "U4") (pin "A5") (pinfunction "1_A5") (pintype "input"))
    )
    (net (code "39") (name "Net-(R6-Pad2)") (class "Default")
      (node (ref "R6") (pin "2") (pinfunction "2_2") (pintype "input"))
      (node (ref "U4") (pin "B5") (pinfunction "1_B5") (pintype "input"))
    )
    (net (code "40") (name "Net-(U7-OUTPUT)") (class "Default")
      (node (ref "D1") (pin "1") (pinfunction "1_1") (pintype "input"))
      (node (ref "L2") (pin "2") (pinfunction "2_2") (pintype "input"))
      (node (ref "U7") (pin "2") (pinfunction "OUTPUT_2") (pintype "input"))
    )
    (net (code "41") (name "OSC32_IN") (class "Default")
      (node (ref "C12") (pin "1") (pinfunction "1_1") (pintype "input"))
      (node (ref "U1") (pin "3") (pinfunction "PC14-OSC32_IN_3") (pintype "input"))
      (node (ref "X3") (pin "2") (pinfunction "2_2") (pintype "input"))
    )
    (net (code "42") (name "OSC32_OUT") (class "Default")
      (node (ref "C11") (pin "2") (pinfunction "2_2") (pintype "input"))
      (node (ref "U1") (pin "4") (pinfunction "PC15-OSC32_OUT_4") (pintype "input"))
      (node (ref "X3") (pin "1") (pinfunction "1_1") (pintype "input"))
    )
    (net (code "43") (name "OSC_IN") (class "Default")
      (node (ref "C9") (pin "2") (pinfunction "2_2") (pintype "input"))
      (node (ref "R13") (pin "2") (pinfunction "2_2") (pintype "input"))
      (node (ref "U1") (pin "5") (pinfunction "PDO-OSC_IN_5") (pintype "input"))
      (node (ref "X2") (pin "3") (pinfunction "3_3") (pintype "input"))
    )
    (net (code "44") (name "OSC_OUT") (class "Default")
      (node (ref "C10") (pin "2") (pinfunction "2_2") (pintype "input"))
      (node (ref "R13") (pin "1") (pinfunction "1_1") (pintype "input"))
      (node (ref "U1") (pin "6") (pinfunction "PD1-OSC_OUT_6") (pintype "input"))
      (node (ref "X2") (pin "1") (pinfunction "1_1") (pintype "input"))
    )
    (net (code "45") (name "POWER") (class "Default")
      (node (ref "CN2") (pin "1") (pinfunction "+_1") (pintype "input"))
      (node (ref "CN3") (pin "1") (pinfunction "1_1") (pintype "input"))
      (node (ref "U10") (pin "2") (pinfunction "2_2") (pintype "input"))
      (node (ref "U11") (pin "1") (pinfunction "1_1") (pintype "input"))
    )
    (net (code "46") (name "PWM1") (class "Default")
      (node (ref "U1") (pin "37") (pinfunction "PC6_37") (pintype "input"))
      (node (ref "U12") (pin "23") (pinfunction "PWMA_23") (pintype "input"))
    )
    (net (code "47") (name "PWM2") (class "Default")
      (node (ref "U1") (pin "38") (pinfunction "PC7_38") (pintype "input"))
      (node (ref "U12") (pin "15") (pinfunction "PWMB_15") (pintype "input"))
    )
    (net (code "48") (name "PWM3") (class "Default")
      (node (ref "U1") (pin "39") (pinfunction "PC8_39") (pintype "input"))
      (node (ref "U13") (pin "23") (pinfunction "PWMA_23") (pintype "input"))
    )
    (net (code "49") (name "PWM4") (class "Default")
      (node (ref "U1") (pin "40") (pinfunction "PC9_40") (pintype "input"))
      (node (ref "U13") (pin "15") (pinfunction "PWMB_15") (pintype "input"))
    )
    (net (code "50") (name "SPI1_BLK") (class "Default")
      (node (ref "H7") (pin "8") (pinfunction "8_8") (pintype "input"))
      (node (ref "U1") (pin "26") (pinfunction "PB0_26") (pintype "input"))
    )
    (net (code "51") (name "SPI1_CLK") (class "Default")
      (node (ref "H7") (pin "3") (pinfunction "3_3") (pintype "input"))
      (node (ref "U1") (pin "21") (pinfunction "PA5_21") (pintype "input"))
    )
    (net (code "52") (name "SPI1_CS") (class "Default")
      (node (ref "H7") (pin "7") (pinfunction "7_7") (pintype "input"))
      (node (ref "U1") (pin "25") (pinfunction "PC5_25") (pintype "input"))
    )
    (net (code "53") (name "SPI1_DC") (class "Default")
      (node (ref "H7") (pin "6") (pinfunction "6_6") (pintype "input"))
      (node (ref "U1") (pin "24") (pinfunction "PC4_24") (pintype "input"))
    )
    (net (code "54") (name "SPI1_MISO") (class "Default")
      (node (ref "U1") (pin "22") (pinfunction "PA6_22") (pintype "input"))
    )
    (net (code "55") (name "SPI1_MOSI") (class "Default")
      (node (ref "H7") (pin "4") (pinfunction "4_4") (pintype "input"))
      (node (ref "U1") (pin "23") (pinfunction "PA7_23") (pintype "input"))
    )
    (net (code "56") (name "SPI1_RST") (class "Default")
      (node (ref "H7") (pin "5") (pinfunction "5_5") (pintype "input"))
      (node (ref "U1") (pin "20") (pinfunction "PA4_20") (pintype "input"))
    )
    (net (code "57") (name "SWCLK") (class "Default")
      (node (ref "H9") (pin "2") (pinfunction "2_2") (pintype "input"))
      (node (ref "R25") (pin "2") (pinfunction "2_2") (pintype "input"))
      (node (ref "U1") (pin "49") (pinfunction "PA14_49") (pintype "input"))
    )
    (net (code "58") (name "SWDIO") (class "Default")
      (node (ref "H9") (pin "4") (pinfunction "4_4") (pintype "input"))
      (node (ref "R26") (pin "1") (pinfunction "1_1") (pintype "input"))
      (node (ref "U1") (pin "46") (pinfunction "PA13_46") (pintype "input"))
    )
    (net (code "59") (name "SW_1") (class "Default")
      (node (ref "R21") (pin "2") (pinfunction "2_2") (pintype "input"))
      (node (ref "SW2") (pin "6") (pinfunction "PIN6_6") (pintype "input"))
      (node (ref "U1") (pin "8") (pinfunction "PC0_8") (pintype "input"))
    )
    (net (code "60") (name "SW_2") (class "Default")
      (node (ref "R22") (pin "2") (pinfunction "2_2") (pintype "input"))
      (node (ref "SW2") (pin "5") (pinfunction "PIN5_5") (pintype "input"))
      (node (ref "U1") (pin "9") (pinfunction "PC1_9") (pintype "input"))
    )
    (net (code "61") (name "SW_3") (class "Default")
      (node (ref "R23") (pin "2") (pinfunction "2_2") (pintype "input"))
      (node (ref "SW2") (pin "4") (pinfunction "PIN4_4") (pintype "input"))
      (node (ref "U1") (pin "10") (pinfunction "PC2_10") (pintype "input"))
    )
    (net (code "62") (name "TIM2_CH1") (class "Default")
      (node (ref "H4") (pin "3") (pinfunction "3_3") (pintype "input"))
      (node (ref "U1") (pin "50") (pinfunction "PA15_50") (pintype "input"))
    )
    (net (code "63") (name "TIM2_CH2") (class "Default")
      (node (ref "H4") (pin "4") (pinfunction "4_4") (pintype "input"))
      (node (ref "U1") (pin "55") (pinfunction "PB3_55") (pintype "input"))
    )
    (net (code "64") (name "TIM3_CH1") (class "Default")
      (node (ref "H3") (pin "3") (pinfunction "3_3") (pintype "input"))
      (node (ref "U1") (pin "56") (pinfunction "PB4_56") (pintype "input"))
    )
    (net (code "65") (name "TIM3_CH2") (class "Default")
      (node (ref "H3") (pin "4") (pinfunction "4_4") (pintype "input"))
      (node (ref "U1") (pin "57") (pinfunction "PB5_57") (pintype "input"))
    )
    (net (code "66") (name "TIM4_CH1") (class "Default")
      (node (ref "H5") (pin "3") (pinfunction "3_3") (pintype "input"))
      (node (ref "U1") (pin "58") (pinfunction "PB6_58") (pintype "input"))
    )
    (net (code "67") (name "TIM4_CH2") (class "Default")
      (node (ref "H5") (pin "4") (pinfunction "4_4") (pintype "input"))
      (node (ref "U1") (pin "59") (pinfunction "PB7_59") (pintype "input"))
    )
    (net (code "68") (name "TIM5_CH1") (class "Default")
      (node (ref "H6") (pin "3") (pinfunction "3_3") (pintype "input"))
      (node (ref "U1") (pin "14") (pinfunction "PA0-WKUP_14") (pintype "input"))
    )
    (net (code "69") (name "TIM5_CH2") (class "Default")
      (node (ref "H6") (pin "4") (pinfunction "4_4") (pintype "input"))
      (node (ref "U1") (pin "15") (pinfunction "PA1_15") (pintype "input"))
    )
    (net (code "70") (name "USART1_RX") (class "Default")
      (node (ref "R2") (pin "2") (pinfunction "2_2") (pintype "input"))
      (node (ref "U1") (pin "43") (pinfunction "PA10_43") (pintype "input"))
    )
    (net (code "71") (name "USART1_TX") (class "Default")
      (node (ref "R4") (pin "2") (pinfunction "2_2") (pintype "input"))
      (node (ref "U1") (pin "42") (pinfunction "PA9_42") (pintype "input"))
    )
    (net (code "72") (name "USART2_RX") (class "Default")
      (node (ref "CN4") (pin "3") (pinfunction "3_3") (pintype "input"))
      (node (ref "H10") (pin "3") (pinfunction "3_3") (pintype "unspecified"))
      (node (ref "U1") (pin "17") (pinfunction "PA3_17") (pintype "input"))
    )
    (net (code "73") (name "USART2_TX") (class "Default")
      (node (ref "CN4") (pin "4") (pinfunction "4_4") (pintype "input"))
      (node (ref "H10") (pin "4") (pinfunction "4_4") (pintype "unspecified"))
      (node (ref "U1") (pin "16") (pinfunction "PA2_16") (pintype "input"))
    )
    (net (code "74") (name "USB_DN_IN") (class "Default")
      (node (ref "U3") (pin "6") (pinfunction "D-_6") (pintype "input"))
      (node (ref "U4") (pin "A7") (pinfunction "1_A7") (pintype "input"))
      (node (ref "U4") (pin "B7") (pinfunction "1_B7") (pintype "input"))
    )
    (net (code "75") (name "USB_DP_IN") (class "Default")
      (node (ref "U3") (pin "5") (pinfunction "D+_5") (pintype "input"))
      (node (ref "U4") (pin "A6") (pinfunction "1_A6") (pintype "input"))
      (node (ref "U4") (pin "B6") (pinfunction "1_B6") (pintype "input"))
    )
    (net (code "76") (name "VCC") (class "Default")
      (node (ref "C14") (pin "2") (pinfunction "2_2") (pintype "input"))
      (node (ref "C15") (pin "2") (pinfunction "2_2") (pintype "input"))
      (node (ref "C16") (pin "2") (pinfunction "2_2") (pintype "input"))
      (node (ref "C17") (pin "2") (pinfunction "2_2") (pintype "input"))
      (node (ref "C18") (pin "2") (pinfunction "2_2") (pintype "input"))
      (node (ref "C24") (pin "2") (pinfunction "2_2") (pintype "input"))
      (node (ref "C8") (pin "2") (pinfunction "2_2") (pintype "input"))
      (node (ref "CN4") (pin "1") (pinfunction "1_1") (pintype "input"))
      (node (ref "H1") (pin "1") (pinfunction "1_1") (pintype "input"))
      (node (ref "H1") (pin "2") (pinfunction "2_2") (pintype "input"))
      (node (ref "H10") (pin "1") (pinfunction "1_1") (pintype "unspecified"))
      (node (ref "H7") (pin "2") (pinfunction "2_2") (pintype "input"))
      (node (ref "H8") (pin "1") (pinfunction "1_1") (pintype "input"))
      (node (ref "H9") (pin "1") (pinfunction "1_1") (pintype "input"))
      (node (ref "R14") (pin "2") (pinfunction "2_2") (pintype "input"))
      (node (ref "R18") (pin "2") (pinfunction "2_2") (pintype "input"))
      (node (ref "R21") (pin "1") (pinfunction "1_1") (pintype "input"))
      (node (ref "R22") (pin "1") (pinfunction "1_1") (pintype "input"))
      (node (ref "R23") (pin "1") (pinfunction "1_1") (pintype "input"))
      (node (ref "R26") (pin "2") (pinfunction "2_2") (pintype "input"))
      (node (ref "U1") (pin "1") (pinfunction "VBAT_1") (pintype "input"))
      (node (ref "U1") (pin "13") (pinfunction "VDDA_13") (pintype "input"))
      (node (ref "U1") (pin "19") (pinfunction "VDD_4_19") (pintype "input"))
      (node (ref "U1") (pin "32") (pinfunction "VDD_1_32") (pintype "input"))
      (node (ref "U1") (pin "48") (pinfunction "VDD_2_48") (pintype "input"))
      (node (ref "U1") (pin "64") (pinfunction "VDD_3_64") (pintype "input"))
      (node (ref "U3") (pin "16") (pinfunction "VCC_16") (pintype "input"))
      (node (ref "U3") (pin "4") (pinfunction "V3_4") (pintype "input"))
      (node (ref "U8") (pin "2") (pinfunction "VOUT_2") (pintype "input"))
      (node (ref "U8") (pin "4") (pinfunction "VOUT_4") (pintype "input"))
    )
    (net (code "77") (name "unconnected-(CN4-Pad5)") (class "Default")
      (node (ref "CN4") (pin "5") (pinfunction "5_5") (pintype "input"))
    )
    (net (code "78") (name "unconnected-(CN4-Pad6)") (class "Default")
      (node (ref "CN4") (pin "6") (pinfunction "6_6") (pintype "input"))
    )
    (net (code "79") (name "unconnected-(H8-Pad5)") (class "Default")
      (node (ref "H8") (pin "5") (pinfunction "5_5") (pintype "input+no_connect"))
    )
    (net (code "80") (name "unconnected-(H8-Pad6)") (class "Default")
      (node (ref "H8") (pin "6") (pinfunction "6_6") (pintype "input+no_connect"))
    )
    (net (code "81") (name "unconnected-(H8-Pad7)") (class "Default")
      (node (ref "H8") (pin "7") (pinfunction "7_7") (pintype "input+no_connect"))
    )
    (net (code "82") (name "unconnected-(H8-Pad8)") (class "Default")
      (node (ref "H8") (pin "8") (pinfunction "8_8") (pintype "input+no_connect"))
    )
    (net (code "83") (name "unconnected-(H8-Pad9)") (class "Default")
      (node (ref "H8") (pin "9") (pinfunction "9_9") (pintype "input+no_connect"))
    )
    (net (code "84") (name "unconnected-(U1-PB1-Pad27)") (class "Default")
      (node (ref "U1") (pin "27") (pinfunction "PB1_27") (pintype "input"))
    )
    (net (code "85") (name "unconnected-(U1-PC3-Pad11)") (class "Default")
      (node (ref "U1") (pin "11") (pinfunction "PC3_11") (pintype "input"))
    )
    (net (code "86") (name "unconnected-(U3-CTS#-Pad9)") (class "Default")
      (node (ref "U3") (pin "9") (pinfunction "CTS#_9") (pintype "input+no_connect"))
    )
    (net (code "87") (name "unconnected-(U3-DCD#-Pad12)") (class "Default")
      (node (ref "U3") (pin "12") (pinfunction "DCD#_12") (pintype "input+no_connect"))
    )
    (net (code "88") (name "unconnected-(U3-DSR#-Pad10)") (class "Default")
      (node (ref "U3") (pin "10") (pinfunction "DSR#_10") (pintype "input+no_connect"))
    )
    (net (code "89") (name "unconnected-(U3-DTR#-Pad13)") (class "Default")
      (node (ref "U3") (pin "13") (pinfunction "DTR#_13") (pintype "input+no_connect"))
    )
    (net (code "90") (name "unconnected-(U3-NC.-Pad7)") (class "Default")
      (node (ref "U3") (pin "7") (pinfunction "NC._7") (pintype "input+no_connect"))
    )
    (net (code "91") (name "unconnected-(U3-NC.-Pad8)") (class "Default")
      (node (ref "U3") (pin "8") (pinfunction "NC._8") (pintype "input+no_connect"))
    )
    (net (code "92") (name "unconnected-(U3-R232-Pad15)") (class "Default")
      (node (ref "U3") (pin "15") (pinfunction "R232_15") (pintype "input+no_connect"))
    )
    (net (code "93") (name "unconnected-(U3-RI#-Pad11)") (class "Default")
      (node (ref "U3") (pin "11") (pinfunction "RI#_11") (pintype "input+no_connect"))
    )
    (net (code "94") (name "unconnected-(U3-RTS#-Pad14)") (class "Default")
      (node (ref "U3") (pin "14") (pinfunction "RTS#_14") (pintype "input+no_connect"))
    )
    (net (code "95") (name "unconnected-(U4-1-PadA8)") (class "Default")
      (node (ref "U4") (pin "A8") (pinfunction "1_A8") (pintype "input+no_connect"))
    )
    (net (code "96") (name "unconnected-(U4-1-PadB8)") (class "Default")
      (node (ref "U4") (pin "B8") (pinfunction "1_B8") (pintype "input+no_connect"))
    )
    (net (code "97") (name "unconnected-(U10-Pad3)") (class "Default")
      (node (ref "U10") (pin "3") (pinfunction "3_3") (pintype "input"))
    )
    (net (code "98") (name "unconnected-(U10-Pad4)") (class "Default")
      (node (ref "U10") (pin "4") (pinfunction "4_4") (pintype "input"))
    )
    (net (code "99") (name "unconnected-(U10-Pad5)") (class "Default")
      (node (ref "U10") (pin "5") (pinfunction "5_5") (pintype "input"))
    )
    (net (code "100") (name "unconnected-(X2-Pad2)") (class "Default")
      (node (ref "X2") (pin "2") (pinfunction "2_2") (pintype "input"))
    )
    (net (code "101") (name "unconnected-(X2-Pad4)") (class "Default")
      (node (ref "X2") (pin "4") (pinfunction "4_4") (pintype "input"))
    )
  )
)
